# MOOG_AC2690_toSPI_Commutator_Board.net
KiCad netlist of a schematic drawn in EAGLE
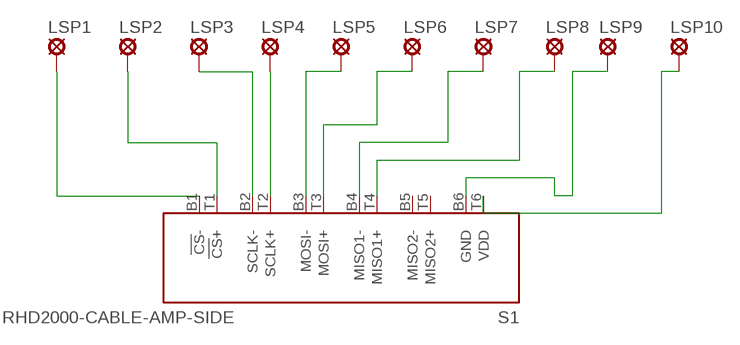
[diagram p0: schematic, sheet 1]

(export (version "E")
  (design (tool "Eeschema 10.0.6"))
  (components
    (comp (ref "LSP1")
      (value "LSP11")
      (footprint "eagle-import:LSP11")
      (libsource (lib "eagle-import") (part "LSP11"))
    )
    (comp (ref "LSP2")
      (value "LSP11")
      (footprint "eagle-import:LSP11")
      (libsource (lib "eagle-import") (part "LSP11"))
    )
    (comp (ref "LSP3")
      (value "LSP11")
      (footprint "eagle-import:LSP11")
      (libsource (lib "eagle-import") (part "LSP11"))
    )
    (comp (ref "LSP4")
      (value "LSP11")
      (footprint "eagle-import:LSP11")
      (libsource (lib "eagle-import") (part "LSP11"))
    )
    (comp (ref "LSP5")
      (value "LSP11")
      (footprint "eagle-import:LSP11")
      (libsource (lib "eagle-import") (part "LSP11"))
    )
    (comp (ref "LSP6")
      (value "LSP11")
      (footprint "eagle-import:LSP11")
      (libsource (lib "eagle-import") (part "LSP11"))
    )
    (comp (ref "LSP7")
      (value "LSP11")
      (footprint "eagle-import:LSP11")
      (libsource (lib "eagle-import") (part "LSP11"))
    )
    (comp (ref "LSP8")
      (value "LSP11")
      (footprint "eagle-import:LSP11")
      (libsource (lib "eagle-import") (part "LSP11"))
    )
    (comp (ref "LSP9")
      (value "LSP11")
      (footprint "eagle-import:LSP11")
      (libsource (lib "eagle-import") (part "LSP11"))
    )
    (comp (ref "LSP10")
      (value "LSP11")
      (footprint "eagle-import:LSP11")
      (libsource (lib "eagle-import") (part "LSP11"))
    )
    (comp (ref "S1")
      (value "RHD2000-CABLE-AMP-SIDE")
      (footprint "eagle-import:OMNETICS_PZN-12-AA")
      (libsource (lib "eagle-import") (part "RHD2000-CABLE-AMP-SIDE"))
    )
  )
  (nets
    (net (code "1") (name "Net-(S1-GND)") (class "Default")
      (node (ref "LSP9") (pin "MP") (pinfunction "MP_MP") (pintype "passive"))
      (node (ref "S1") (pin "B6") (pinfunction "GND_B6") (pintype "power_in"))
    )
    (net (code "2") (name "Net-(S1-MISO1+)") (class "Default")
      (node (ref "LSP8") (pin "MP") (pinfunction "MP_MP") (pintype "passive"))
      (node (ref "S1") (pin "T4") (pinfunction "MISO1+_T4") (pintype "bidirectional"))
    )
    (net (code "3") (name "Net-(S1-MISO1-)") (class "Default")
      (node (ref "LSP7") (pin "MP") (pinfunction "MP_MP") (pintype "passive"))
      (node (ref "S1") (pin "B4") (pinfunction "MISO1-_B4") (pintype "bidirectional"))
    )
    (net (code "4") (name "Net-(S1-MOSI+)") (class "Default")
      (node (ref "LSP6") (pin "MP") (pinfunction "MP_MP") (pintype "passive"))
      (node (ref "S1") (pin "T3") (pinfunction "MOSI+_T3") (pintype "bidirectional"))
    )
    (net (code "5") (name "Net-(S1-MOSI-)") (class "Default")
      (node (ref "LSP5") (pin "MP") (pinfunction "MP_MP") (pintype "passive"))
      (node (ref "S1") (pin "B3") (pinfunction "MOSI-_B3") (pintype "bidirectional"))
    )
    (net (code "6") (name "Net-(S1-SCLK+)") (class "Default")
      (node (ref "LSP4") (pin "MP") (pinfunction "MP_MP") (pintype "passive"))
      (node (ref "S1") (pin "T2") (pinfunction "SCLK+_T2") (pintype "bidirectional"))
    )
    (net (code "7") (name "Net-(S1-SCLK-)") (class "Default")
      (node (ref "LSP3") (pin "MP") (pinfunction "MP_MP") (pintype "passive"))
      (node (ref "S1") (pin "B2") (pinfunction "SCLK-_B2") (pintype "bidirectional"))
    )
    (net (code "8") (name "Net-(S1-VDD)") (class "Default")
      (node (ref "LSP10") (pin "MP") (pinfunction "MP_MP") (pintype "passive"))
      (node (ref "S1") (pin "T6") (pinfunction "VDD_T6") (pintype "bidirectional"))
    )
    (net (code "9") (name "Net-(S1-~{CS}+)") (class "Default")
      (node (ref "LSP2") (pin "MP") (pinfunction "MP_MP") (pintype "passive"))
      (node (ref "S1") (pin "T1") (pinfunction "~{CS}+_T1") (pintype "bidirectional"))
    )
    (net (code "10") (name "Net-(S1-~{CS}-)") (class "Default")
      (node (ref "LSP1") (pin "MP") (pinfunction "MP_MP") (pintype "passive"))
      (node (ref "S1") (pin "B1") (pinfunction "~{CS}-_B1") (pintype "bidirectional"))
    )
    (net (code "11") (name "unconnected-(S1-MISO2+-PadT5)") (class "Default")
      (node (ref "S1") (pin "T5") (pinfunction "MISO2+_T5") (pintype "bidirectional"))
    )
    (net (code "12") (name "unconnected-(S1-MISO2--PadB5)") (class "Default")
      (node (ref "S1") (pin "B5") (pinfunction "MISO2-_B5") (pintype "bidirectional"))
    )
  )
)
